# spi_sd.net
KiCad netlist of a schematic drawn in EAGLE
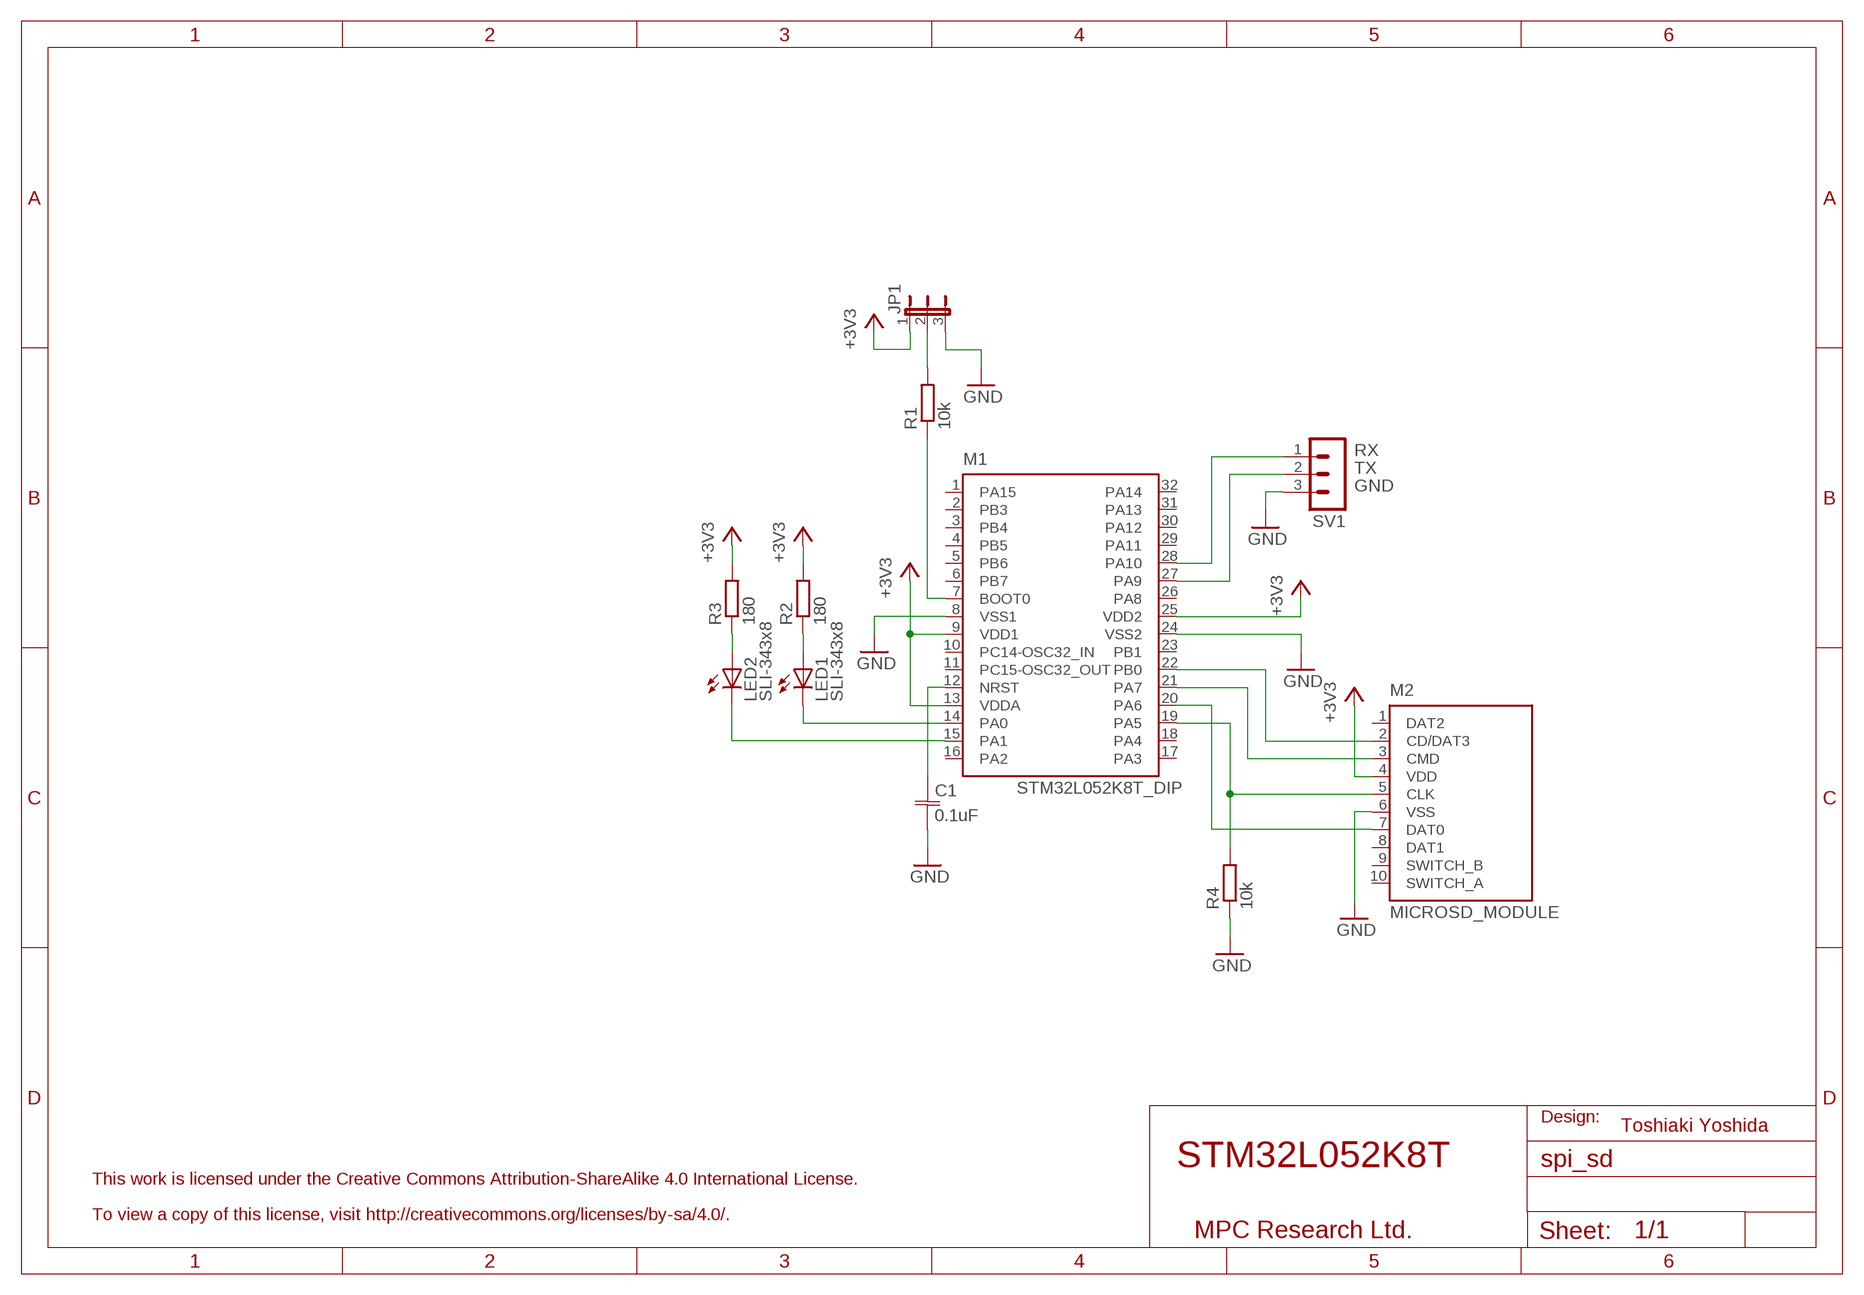
[diagram p0: schematic, sheet 1]

(export (version "E")
  (design (tool "Eeschema 10.0.6"))
  (components
    (comp (ref "C1")
      (value "0.1uF")
      (footprint "eagle-import:C050-024X044")
      (libsource (lib "eagle-import") (part "C-JIS050-024X044"))
    )
    (comp (ref "JP1")
      (value "JP2E")
      (footprint "eagle-import:JP2")
      (libsource (lib "eagle-import") (part "JP2E"))
    )
    (comp (ref "LED1")
      (value "SLI-343x8")
      (footprint "eagle-import:LED3MM")
      (libsource (lib "eagle-import") (part "LED3MM"))
    )
    (comp (ref "LED2")
      (value "SLI-343x8")
      (footprint "eagle-import:LED3MM")
      (libsource (lib "eagle-import") (part "LED3MM"))
    )
    (comp (ref "M1")
      (value "STM32L052K8T_DIP")
      (footprint "eagle-import:DIP32")
      (libsource (lib "eagle-import") (part "STM32L052K8T_DIP"))
    )
    (comp (ref "M2")
      (value "MICROSD_MODULE")
      (footprint "eagle-import:MICROSD")
      (libsource (lib "eagle-import") (part "MICROSD_MODULE"))
    )
    (comp (ref "R1")
      (value "10k")
      (footprint "eagle-import:0207_2V")
      (libsource (lib "eagle-import") (part "R-EU_0207/2V"))
    )
    (comp (ref "R2")
      (value "180")
      (footprint "eagle-import:0207_2V")
      (libsource (lib "eagle-import") (part "R-EU_0207/2V"))
    )
    (comp (ref "R3")
      (value "180")
      (footprint "eagle-import:0207_2V")
      (libsource (lib "eagle-import") (part "R-EU_0207/2V"))
    )
    (comp (ref "R4")
      (value "10k")
      (footprint "eagle-import:0207_2V")
      (libsource (lib "eagle-import") (part "R-EU_0207/2V"))
    )
    (comp (ref "SV1")
      (value "MA03-1")
      (footprint "eagle-import:MA03-1")
      (libsource (lib "eagle-import") (part "MA03-1"))
    )
  )
  (nets
    (net (code "1") (name "+3V3") (class "Default")
      (node (ref "JP1") (pin "1") (pinfunction "1_1") (pintype "passive"))
      (node (ref "M1") (pin "13") (pinfunction "VDDA_13") (pintype "power_in"))
      (node (ref "M1") (pin "25") (pinfunction "VDD2_25") (pintype "bidirectional"))
      (node (ref "M1") (pin "9") (pinfunction "VDD1_9") (pintype "power_in"))
      (node (ref "M2") (pin "4") (pinfunction "VDD_4") (pintype "power_in"))
      (node (ref "R2") (pin "2") (pinfunction "2_2") (pintype "passive"))
      (node (ref "R3") (pin "2") (pinfunction "2_2") (pintype "passive"))
    )
    (net (code "2") (name "GND") (class "Default")
      (node (ref "C1") (pin "2") (pinfunction "2_2") (pintype "passive"))
      (node (ref "JP1") (pin "3") (pinfunction "3_3") (pintype "passive"))
      (node (ref "M1") (pin "24") (pinfunction "VSS2_24") (pintype "power_in"))
      (node (ref "M1") (pin "8") (pinfunction "VSS1_8") (pintype "power_in"))
      (node (ref "M2") (pin "6") (pinfunction "VSS_6") (pintype "power_in"))
      (node (ref "R4") (pin "1") (pinfunction "1_1") (pintype "passive"))
      (node (ref "SV1") (pin "3") (pinfunction "3_3") (pintype "passive"))
    )
    (net (code "3") (name "Net-(JP1-Pad2)") (class "Default")
      (node (ref "JP1") (pin "2") (pinfunction "2_2") (pintype "passive"))
      (node (ref "R1") (pin "2") (pinfunction "2_2") (pintype "passive"))
    )
    (net (code "4") (name "Net-(LED1-C)") (class "Default")
      (node (ref "LED1") (pin "K") (pinfunction "C_K") (pintype "passive"))
      (node (ref "M1") (pin "14") (pinfunction "PA0_14") (pintype "bidirectional"))
    )
    (net (code "5") (name "Net-(LED1-PadA)") (class "Default")
      (node (ref "LED1") (pin "A") (pinfunction "A_A") (pintype "passive"))
      (node (ref "R2") (pin "1") (pinfunction "1_1") (pintype "passive"))
    )
    (net (code "6") (name "Net-(LED2-C)") (class "Default")
      (node (ref "LED2") (pin "K") (pinfunction "C_K") (pintype "passive"))
      (node (ref "M1") (pin "15") (pinfunction "PA1_15") (pintype "bidirectional"))
    )
    (net (code "7") (name "Net-(LED2-PadA)") (class "Default")
      (node (ref "LED2") (pin "A") (pinfunction "A_A") (pintype "passive"))
      (node (ref "R3") (pin "1") (pinfunction "1_1") (pintype "passive"))
    )
    (net (code "8") (name "Net-(M1-BOOT0)") (class "Default")
      (node (ref "M1") (pin "7") (pinfunction "BOOT0_7") (pintype "bidirectional"))
      (node (ref "R1") (pin "1") (pinfunction "1_1") (pintype "passive"))
    )
    (net (code "9") (name "Net-(M1-NRST)") (class "Default")
      (node (ref "C1") (pin "1") (pinfunction "1_1") (pintype "passive"))
      (node (ref "M1") (pin "12") (pinfunction "NRST_12") (pintype "bidirectional"))
    )
    (net (code "10") (name "Net-(M1-PA5)") (class "Default")
      (node (ref "M1") (pin "19") (pinfunction "PA5_19") (pintype "bidirectional"))
      (node (ref "M2") (pin "5") (pinfunction "CLK_5") (pintype "input"))
      (node (ref "R4") (pin "2") (pinfunction "2_2") (pintype "passive"))
    )
    (net (code "11") (name "Net-(M1-PA6)") (class "Default")
      (node (ref "M1") (pin "20") (pinfunction "PA6_20") (pintype "bidirectional"))
      (node (ref "M2") (pin "7") (pinfunction "DAT0_7") (pintype "bidirectional"))
    )
    (net (code "12") (name "Net-(M1-PA7)") (class "Default")
      (node (ref "M1") (pin "21") (pinfunction "PA7_21") (pintype "bidirectional"))
      (node (ref "M2") (pin "3") (pinfunction "CMD_3") (pintype "bidirectional"))
    )
    (net (code "13") (name "Net-(M1-PA9)") (class "Default")
      (node (ref "M1") (pin "27") (pinfunction "PA9_27") (pintype "bidirectional"))
      (node (ref "SV1") (pin "2") (pinfunction "2_2") (pintype "passive"))
    )
    (net (code "14") (name "Net-(M1-PA10)") (class "Default")
      (node (ref "M1") (pin "28") (pinfunction "PA10_28") (pintype "bidirectional"))
      (node (ref "SV1") (pin "1") (pinfunction "1_1") (pintype "passive"))
    )
    (net (code "15") (name "Net-(M1-PB0)") (class "Default")
      (node (ref "M1") (pin "22") (pinfunction "PB0_22") (pintype "bidirectional"))
      (node (ref "M2") (pin "2") (pinfunction "CD/DAT3_2") (pintype "bidirectional"))
    )
    (net (code "16") (name "unconnected-(M1-PA2-Pad16)") (class "Default")
      (node (ref "M1") (pin "16") (pinfunction "PA2_16") (pintype "bidirectional"))
    )
    (net (code "17") (name "unconnected-(M1-PA3-Pad17)") (class "Default")
      (node (ref "M1") (pin "17") (pinfunction "PA3_17") (pintype "bidirectional"))
    )
    (net (code "18") (name "unconnected-(M1-PA4-Pad18)") (class "Default")
      (node (ref "M1") (pin "18") (pinfunction "PA4_18") (pintype "bidirectional"))
    )
    (net (code "19") (name "unconnected-(M1-PA8-Pad26)") (class "Default")
      (node (ref "M1") (pin "26") (pinfunction "PA8_26") (pintype "bidirectional"))
    )
    (net (code "20") (name "unconnected-(M1-PA11-Pad29)") (class "Default")
      (node (ref "M1") (pin "29") (pinfunction "PA11_29") (pintype "bidirectional"))
    )
    (net (code "21") (name "unconnected-(M1-PA12-Pad30)") (class "Default")
      (node (ref "M1") (pin "30") (pinfunction "PA12_30") (pintype "bidirectional"))
    )
    (net (code "22") (name "unconnected-(M1-PA13-Pad31)") (class "Default")
      (node (ref "M1") (pin "31") (pinfunction "PA13_31") (pintype "bidirectional"))
    )
    (net (code "23") (name "unconnected-(M1-PA14-Pad32)") (class "Default")
      (node (ref "M1") (pin "32") (pinfunction "PA14_32") (pintype "bidirectional"))
    )
    (net (code "24") (name "unconnected-(M1-PA15-Pad1)") (class "Default")
      (node (ref "M1") (pin "1") (pinfunction "PA15_1") (pintype "bidirectional"))
    )
    (net (code "25") (name "unconnected-(M1-PB1-Pad23)") (class "Default")
      (node (ref "M1") (pin "23") (pinfunction "PB1_23") (pintype "bidirectional"))
    )
    (net (code "26") (name "unconnected-(M1-PB3-Pad2)") (class "Default")
      (node (ref "M1") (pin "2") (pinfunction "PB3_2") (pintype "bidirectional"))
    )
    (net (code "27") (name "unconnected-(M1-PB4-Pad3)") (class "Default")
      (node (ref "M1") (pin "3") (pinfunction "PB4_3") (pintype "bidirectional"))
    )
    (net (code "28") (name "unconnected-(M1-PB5-Pad4)") (class "Default")
      (node (ref "M1") (pin "4") (pinfunction "PB5_4") (pintype "bidirectional"))
    )
    (net (code "29") (name "unconnected-(M1-PB6-Pad5)") (class "Default")
      (node (ref "M1") (pin "5") (pinfunction "PB6_5") (pintype "bidirectional"))
    )
    (net (code "30") (name "unconnected-(M1-PB7-Pad6)") (class "Default")
      (node (ref "M1") (pin "6") (pinfunction "PB7_6") (pintype "bidirectional"))
    )
    (net (code "31") (name "unconnected-(M1-PC14-OSC32_IN-Pad10)") (class "Default")
      (node (ref "M1") (pin "10") (pinfunction "PC14-OSC32_IN_10") (pintype "bidirectional"))
    )
    (net (code "32") (name "unconnected-(M1-PC15-OSC32_OUT-Pad11)") (class "Default")
      (node (ref "M1") (pin "11") (pinfunction "PC15-OSC32_OUT_11") (pintype "bidirectional"))
    )
    (net (code "33") (name "unconnected-(M2-DAT1-Pad8)") (class "Default")
      (node (ref "M2") (pin "8") (pinfunction "DAT1_8") (pintype "bidirectional"))
    )
    (net (code "34") (name "unconnected-(M2-DAT2-Pad1)") (class "Default")
      (node (ref "M2") (pin "1") (pinfunction "DAT2_1") (pintype "bidirectional"))
    )
    (net (code "35") (name "unconnected-(M2-SWITCH_A-Pad10)") (class "Default")
      (node (ref "M2") (pin "10") (pinfunction "SWITCH_A_10") (pintype "passive"))
    )
    (net (code "36") (name "unconnected-(M2-SWITCH_B-Pad9)") (class "Default")
      (node (ref "M2") (pin "9") (pinfunction "SWITCH_B_9") (pintype "passive"))
    )
  )
)
